# RFM69C_BOB.net
KiCad netlist of a schematic drawn in EAGLE
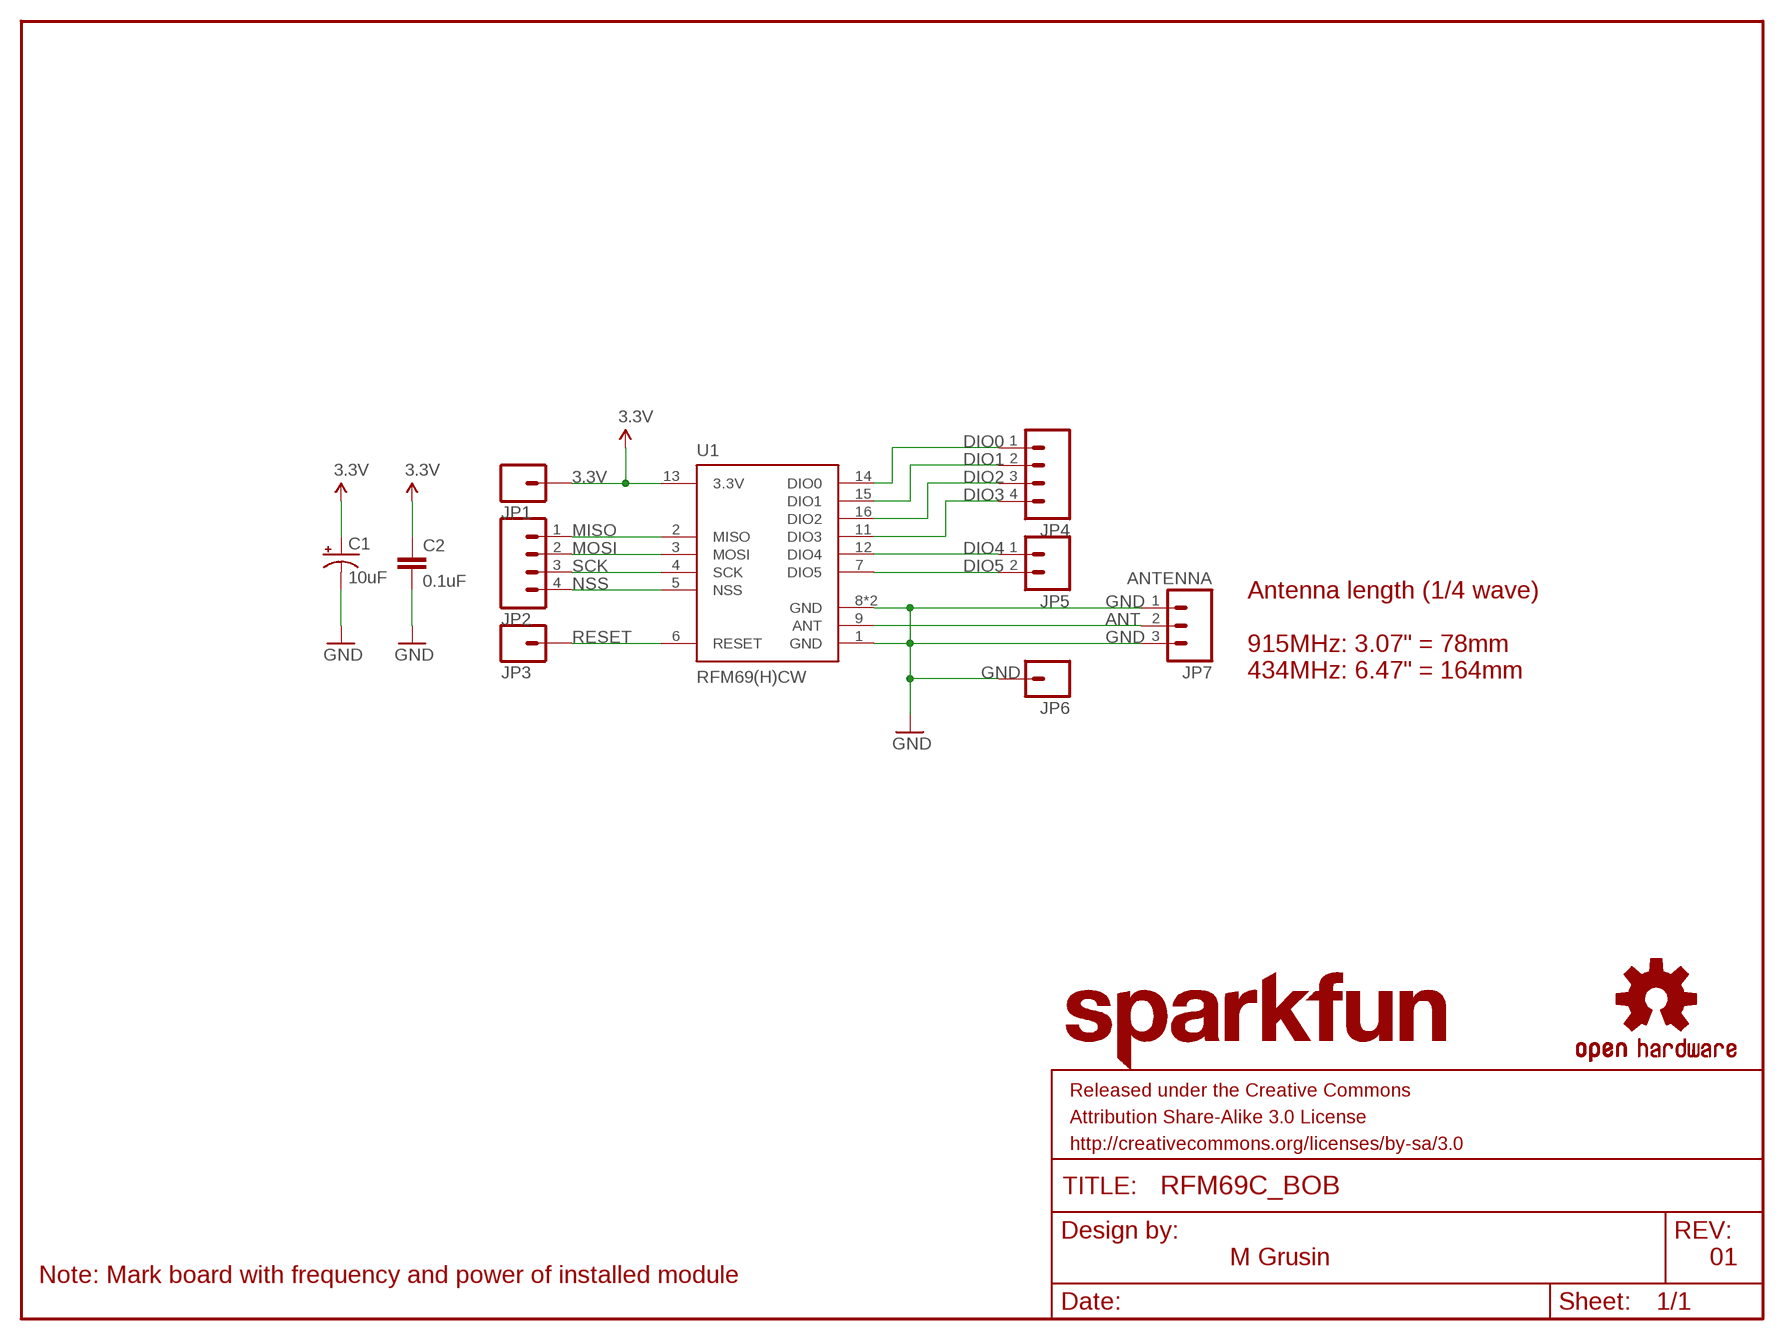
[diagram p0: schematic, sheet 1]

(export (version "E")
  (design (tool "Eeschema 10.0.6"))
  (components
    (comp (ref "C1")
      (value "10uF")
      (footprint "eagle-import:EIA3216")
      (libsource (lib "eagle-import") (part "10UF-16V-10%(TANT)"))
    )
    (comp (ref "C2")
      (value "0.1uF")
      (footprint "eagle-import:0603-CAP")
      (libsource (lib "eagle-import") (part "0.1UF-25V(+80/-20%)(0603)"))
    )
    (comp (ref "FRAME1")
      (value "FRAME-LETTER")
      (footprint "eagle-import:CREATIVE_COMMONS")
      (libsource (lib "eagle-import") (part "FRAME-LETTER"))
    )
    (comp (ref "JP1")
      (value "M01SMDNS")
      (footprint "eagle-import:1X01NS")
      (libsource (lib "eagle-import") (part "M01SMDNS"))
    )
    (comp (ref "JP2")
      (value "M041X04_NO_SILK_ROUND")
      (footprint "eagle-import:1X04_NO_SILK_ROUND")
      (libsource (lib "eagle-import") (part "M041X04_NO_SILK_ROUND"))
    )
    (comp (ref "JP3")
      (value "M01SMDNS")
      (footprint "eagle-import:1X01NS")
      (libsource (lib "eagle-import") (part "M01SMDNS"))
    )
    (comp (ref "JP4")
      (value "M041X04_NO_SILK_ROUND")
      (footprint "eagle-import:1X04_NO_SILK_ROUND")
      (libsource (lib "eagle-import") (part "M041X04_NO_SILK_ROUND"))
    )
    (comp (ref "JP5")
      (value "M021X02_NO_SILK")
      (footprint "eagle-import:1X02_NO_SILK")
      (libsource (lib "eagle-import") (part "M021X02_NO_SILK"))
    )
    (comp (ref "JP6")
      (value "M01SMDNS")
      (footprint "eagle-import:1X01NS")
      (libsource (lib "eagle-import") (part "M01SMDNS"))
    )
    (comp (ref "JP7")
      (value "ANTENNA")
      (footprint "eagle-import:1X03_ROUND_ONLY_NO_SILK")
      (libsource (lib "eagle-import") (part "M03_ROUND_ONLY_NO_SILK"))
    )
    (comp (ref "LOGO1")
      (value "SFE_LOGO_NAME.1_INCH")
      (footprint "eagle-import:SFE_LOGO_NAME_.1")
      (libsource (lib "eagle-import") (part "SFE_LOGO_NAME.1_INCH"))
    )
    (comp (ref "LOGO2")
      (value "OSHW-LOGOS")
      (footprint "eagle-import:OSHW-LOGO-S")
      (libsource (lib "eagle-import") (part "OSHW-LOGOS"))
    )
    (comp (ref "U1")
      (value "RFM69(H)CW")
      (footprint "eagle-import:RFM69CS2")
      (libsource (lib "eagle-import") (part "RFM69CW"))
    )
  )
  (nets
    (net (code "1") (name "/ANT") (class "Default")
      (node (ref "JP7") (pin "2") (pinfunction "2_2") (pintype "passive"))
      (node (ref "U1") (pin "9") (pinfunction "ANT_9") (pintype "passive"))
    )
    (net (code "2") (name "/DIO0") (class "Default")
      (node (ref "JP4") (pin "1") (pinfunction "1_1") (pintype "passive"))
      (node (ref "U1") (pin "14") (pinfunction "DIO0_14") (pintype "bidirectional"))
    )
    (net (code "3") (name "/DIO1") (class "Default")
      (node (ref "JP4") (pin "2") (pinfunction "2_2") (pintype "passive"))
      (node (ref "U1") (pin "15") (pinfunction "DIO1_15") (pintype "bidirectional"))
    )
    (net (code "4") (name "/DIO2") (class "Default")
      (node (ref "JP4") (pin "3") (pinfunction "3_3") (pintype "passive"))
      (node (ref "U1") (pin "16") (pinfunction "DIO2_16") (pintype "bidirectional"))
    )
    (net (code "5") (name "/DIO3") (class "Default")
      (node (ref "JP4") (pin "4") (pinfunction "4_4") (pintype "passive"))
      (node (ref "U1") (pin "11") (pinfunction "DIO3_11") (pintype "bidirectional"))
    )
    (net (code "6") (name "/DIO4") (class "Default")
      (node (ref "JP5") (pin "1") (pinfunction "1_1") (pintype "passive"))
      (node (ref "U1") (pin "12") (pinfunction "DIO4_12") (pintype "bidirectional"))
    )
    (net (code "7") (name "/DIO5") (class "Default")
      (node (ref "JP5") (pin "2") (pinfunction "2_2") (pintype "passive"))
      (node (ref "U1") (pin "7") (pinfunction "DIO5_7") (pintype "bidirectional"))
    )
    (net (code "8") (name "/MISO") (class "Default")
      (node (ref "JP2") (pin "1") (pinfunction "1_1") (pintype "passive"))
      (node (ref "U1") (pin "2") (pinfunction "MISO_2") (pintype "bidirectional"))
    )
    (net (code "9") (name "/MOSI") (class "Default")
      (node (ref "JP2") (pin "2") (pinfunction "2_2") (pintype "passive"))
      (node (ref "U1") (pin "3") (pinfunction "MOSI_3") (pintype "input"))
    )
    (net (code "10") (name "/NSS") (class "Default")
      (node (ref "JP2") (pin "4") (pinfunction "4_4") (pintype "passive"))
      (node (ref "U1") (pin "5") (pinfunction "NSS_5") (pintype "input"))
    )
    (net (code "11") (name "/RESET") (class "Default")
      (node (ref "JP3") (pin "1") (pinfunction "1_1") (pintype "passive"))
      (node (ref "U1") (pin "6") (pinfunction "RESET_6") (pintype "input"))
    )
    (net (code "12") (name "/SCK") (class "Default")
      (node (ref "JP2") (pin "3") (pinfunction "3_3") (pintype "passive"))
      (node (ref "U1") (pin "4") (pinfunction "SCK_4") (pintype "input"))
    )
    (net (code "13") (name "3.3V") (class "Default")
      (node (ref "C1") (pin "A") (pinfunction "+_A") (pintype "passive"))
      (node (ref "C2") (pin "1") (pinfunction "1_1") (pintype "passive"))
      (node (ref "JP1") (pin "1") (pinfunction "1_1") (pintype "passive"))
      (node (ref "U1") (pin "13") (pinfunction "3.3V_13") (pintype "power_in"))
    )
    (net (code "14") (name "GND") (class "Default")
      (node (ref "C1") (pin "C") (pinfunction "-_C") (pintype "passive"))
      (node (ref "C2") (pin "2") (pinfunction "2_2") (pintype "passive"))
      (node (ref "JP6") (pin "1") (pinfunction "1_1") (pintype "passive"))
      (node (ref "JP7") (pin "1") (pinfunction "1_1") (pintype "passive"))
      (node (ref "JP7") (pin "3") (pinfunction "3_3") (pintype "passive"))
      (node (ref "U1") (pin "1") (pinfunction "GND_1") (pintype "power_in"))
      (node (ref "U1") (pin "10") (pinfunction "GND_10") (pintype "power_in"))
      (node (ref "U1") (pin "8") (pinfunction "GND_8") (pintype "power_in"))
    )
  )
)
